# 2x35W_AMP_1_6in_x_1_2in.net
KiCad netlist of a schematic drawn in EAGLE
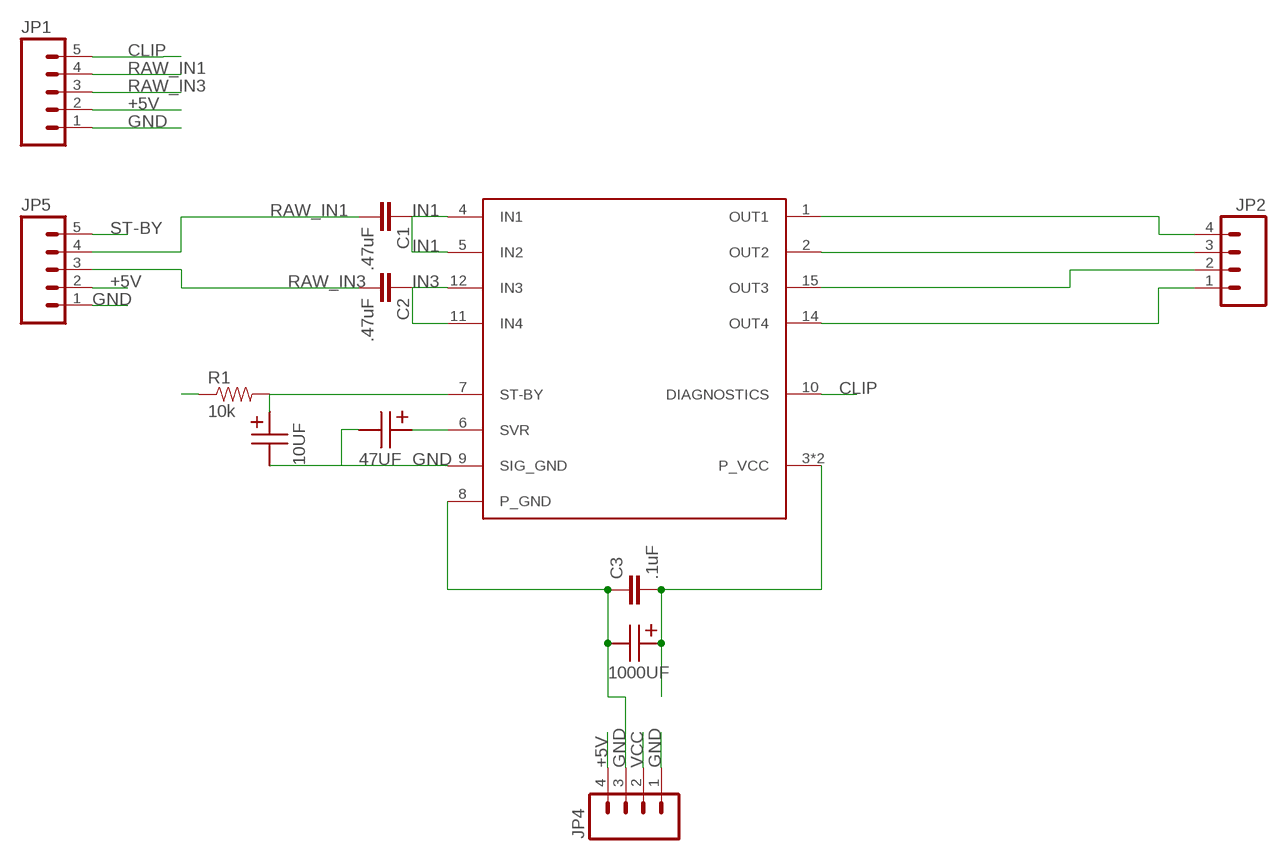
[diagram p0: schematic, sheet 1]

(export (version "E")
  (design (tool "Eeschema 10.0.6"))
  (components
    (comp (ref "10UF")
      (value "5MM-12.5MM-POLAR2MMX5MM")
      (footprint "eagle-import:2MMLEAD_5MMDIAMETER")
      (libsource (lib "eagle-import") (part "5MM-12.5MM-POLAR2MMX5MM"))
    )
    (comp (ref "47UF")
      (value "5MM-12.5MM-POLAR2MMX5MM")
      (footprint "eagle-import:2MMLEAD_5MMDIAMETER")
      (libsource (lib "eagle-import") (part "5MM-12.5MM-POLAR2MMX5MM"))
    )
    (comp (ref "1000UF")
      (value "5MM-12.5MM-POLAR5MMX12.5MM")
      (footprint "eagle-import:5MMLEAD_12.5MMDIAMETER")
      (libsource (lib "eagle-import") (part "5MM-12.5MM-POLAR5MMX12.5MM"))
    )
    (comp (ref "C1")
      (value ".47uF")
      (footprint "eagle-import:1206")
      (libsource (lib "eagle-import") (part "CAP1206"))
    )
    (comp (ref "C2")
      (value ".47uF")
      (footprint "eagle-import:1206")
      (libsource (lib "eagle-import") (part "CAP1206"))
    )
    (comp (ref "C3")
      (value ".1uF")
      (footprint "eagle-import:1206")
      (libsource (lib "eagle-import") (part "CAP1206"))
    )
    (comp (ref "JP1")
      (value "M05SMD2")
      (footprint "eagle-import:1X05-1MM-RA")
      (libsource (lib "eagle-import") (part "M05SMD2"))
    )
    (comp (ref "JP2")
      (value "M04SMD2")
      (footprint "eagle-import:1X04-1MM-RA")
      (libsource (lib "eagle-import") (part "M04SMD2"))
    )
    (comp (ref "JP4")
      (value "M04SMD2")
      (footprint "eagle-import:1X04-1MM-RA")
      (libsource (lib "eagle-import") (part "M04SMD2"))
    )
    (comp (ref "JP5")
      (value "M05SMD2")
      (footprint "eagle-import:1X05-1MM-RA")
      (libsource (lib "eagle-import") (part "M05SMD2"))
    )
    (comp (ref "R1")
      (value "10k")
      (footprint "eagle-import:AXIAL-0.4")
      (libsource (lib "eagle-import") (part "RESISTORPTH-1/4W"))
    )
    (comp (ref "U$1")
      (value "TDA7375V")
      (footprint "eagle-import:MULTIWATT-15")
      (libsource (lib "eagle-import") (part "TDA7375V"))
    )
  )
  (nets
    (net (code "1") (name "/+5V") (class "Default")
      (node (ref "JP1") (pin "2") (pinfunction "2_2") (pintype "passive"))
      (node (ref "JP4") (pin "4") (pinfunction "4_4") (pintype "passive"))
      (node (ref "JP5") (pin "2") (pinfunction "2_2") (pintype "passive"))
    )
    (net (code "2") (name "/CLIP") (class "Default")
      (node (ref "JP1") (pin "5") (pinfunction "5_5") (pintype "passive"))
      (node (ref "U$1") (pin "10") (pinfunction "DIAGNOSTICS_10") (pintype "bidirectional"))
    )
    (net (code "3") (name "/GND") (class "Default")
      (node (ref "1000UF") (pin "-") (pinfunction "-_-") (pintype "bidirectional"))
      (node (ref "10UF") (pin "-") (pinfunction "-_-") (pintype "bidirectional"))
      (node (ref "47UF") (pin "-") (pinfunction "-_-") (pintype "bidirectional"))
      (node (ref "C3") (pin "1") (pinfunction "1_1") (pintype "passive"))
      (node (ref "JP1") (pin "1") (pinfunction "1_1") (pintype "passive"))
      (node (ref "JP4") (pin "1") (pinfunction "1_1") (pintype "passive"))
      (node (ref "JP4") (pin "3") (pinfunction "3_3") (pintype "passive"))
      (node (ref "JP5") (pin "1") (pinfunction "1_1") (pintype "passive"))
      (node (ref "U$1") (pin "8") (pinfunction "P_GND_8") (pintype "bidirectional"))
      (node (ref "U$1") (pin "9") (pinfunction "SIG_GND_9") (pintype "bidirectional"))
    )
    (net (code "4") (name "/IN1") (class "Default")
      (node (ref "C1") (pin "1") (pinfunction "1_1") (pintype "passive"))
      (node (ref "U$1") (pin "4") (pinfunction "IN1_4") (pintype "bidirectional"))
      (node (ref "U$1") (pin "5") (pinfunction "IN2_5") (pintype "bidirectional"))
    )
    (net (code "5") (name "/IN3") (class "Default")
      (node (ref "C2") (pin "1") (pinfunction "1_1") (pintype "passive"))
      (node (ref "U$1") (pin "11") (pinfunction "IN4_11") (pintype "bidirectional"))
      (node (ref "U$1") (pin "12") (pinfunction "IN3_12") (pintype "bidirectional"))
    )
    (net (code "6") (name "/RAW_IN1") (class "Default")
      (node (ref "C1") (pin "2") (pinfunction "2_2") (pintype "passive"))
      (node (ref "JP1") (pin "4") (pinfunction "4_4") (pintype "passive"))
      (node (ref "JP5") (pin "4") (pinfunction "4_4") (pintype "passive"))
    )
    (net (code "7") (name "/RAW_IN3") (class "Default")
      (node (ref "C2") (pin "2") (pinfunction "2_2") (pintype "passive"))
      (node (ref "JP1") (pin "3") (pinfunction "3_3") (pintype "passive"))
      (node (ref "JP5") (pin "3") (pinfunction "3_3") (pintype "passive"))
    )
    (net (code "8") (name "/ST-BY") (class "Default")
      (node (ref "JP5") (pin "5") (pinfunction "5_5") (pintype "passive"))
      (node (ref "R1") (pin "P$1") (pinfunction "1_P$1") (pintype "passive"))
    )
    (net (code "9") (name "/VCC") (class "Default")
      (node (ref "1000UF") (pin "+") (pinfunction "+_+") (pintype "bidirectional"))
      (node (ref "C3") (pin "2") (pinfunction "2_2") (pintype "passive"))
      (node (ref "JP4") (pin "2") (pinfunction "2_2") (pintype "passive"))
      (node (ref "U$1") (pin "13") (pinfunction "P_VCC_13") (pintype "bidirectional"))
      (node (ref "U$1") (pin "3") (pinfunction "P_VCC_3") (pintype "bidirectional"))
    )
    (net (code "10") (name "Net-(R1-2)") (class "Default")
      (node (ref "10UF") (pin "+") (pinfunction "+_+") (pintype "bidirectional"))
      (node (ref "R1") (pin "P$2") (pinfunction "2_P$2") (pintype "passive"))
      (node (ref "U$1") (pin "7") (pinfunction "ST-BY_7") (pintype "bidirectional"))
    )
    (net (code "11") (name "Net-(U$1-OUT1)") (class "Default")
      (node (ref "JP2") (pin "4") (pinfunction "4_4") (pintype "passive"))
      (node (ref "U$1") (pin "1") (pinfunction "OUT1_1") (pintype "bidirectional"))
    )
    (net (code "12") (name "Net-(U$1-OUT2)") (class "Default")
      (node (ref "JP2") (pin "3") (pinfunction "3_3") (pintype "passive"))
      (node (ref "U$1") (pin "2") (pinfunction "OUT2_2") (pintype "bidirectional"))
    )
    (net (code "13") (name "Net-(U$1-OUT3)") (class "Default")
      (node (ref "JP2") (pin "2") (pinfunction "2_2") (pintype "passive"))
      (node (ref "U$1") (pin "15") (pinfunction "OUT3_15") (pintype "bidirectional"))
    )
    (net (code "14") (name "Net-(U$1-OUT4)") (class "Default")
      (node (ref "JP2") (pin "1") (pinfunction "1_1") (pintype "passive"))
      (node (ref "U$1") (pin "14") (pinfunction "OUT4_14") (pintype "bidirectional"))
    )
    (net (code "15") (name "Net-(U$1-SVR)") (class "Default")
      (node (ref "47UF") (pin "+") (pinfunction "+_+") (pintype "bidirectional"))
      (node (ref "U$1") (pin "6") (pinfunction "SVR_6") (pintype "bidirectional"))
    )
  )
)
